# PIC32MK.net
KiCad netlist of a schematic drawn in Altium Designer
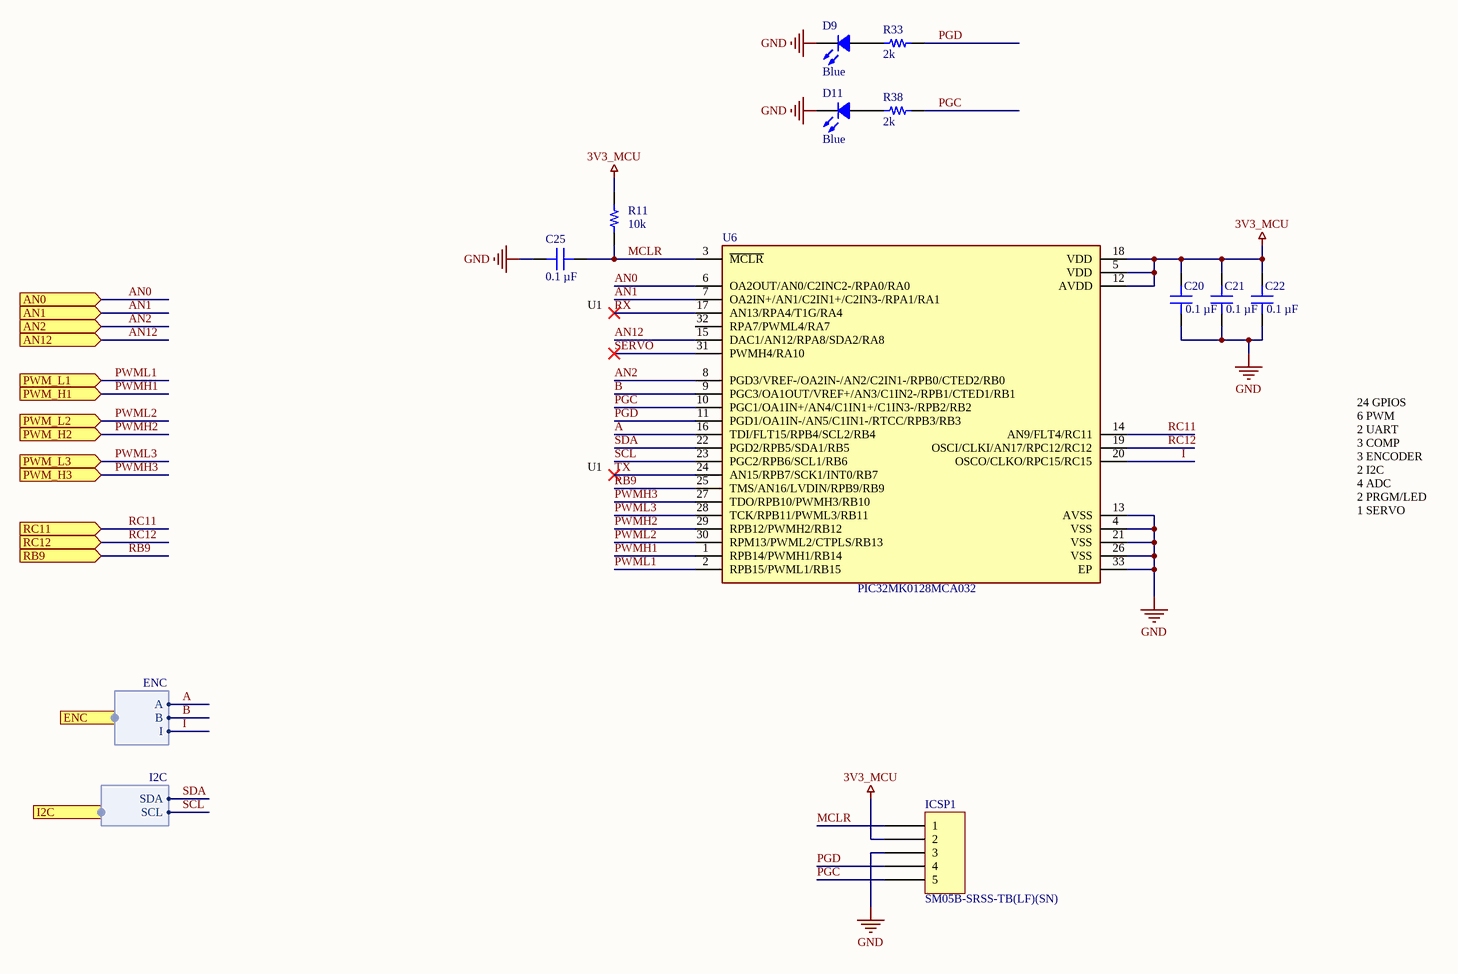
[diagram p0: PIC32MK.SchDoc]

(export (version "E")
  (design (tool "Eeschema 10.0.6"))
  (components
    (comp (ref "C20")
      (value "0.1 µF")
      (footprint "CAP 0402_1005")
      (description "CAP CER 0.1UF 16V X7R 0402")
      (fields (field (name "PART NUMBER") "C0402C104K4RACAUTO") (field (name "MANUFACTURER") "KEMET"))
      (libsource (lib "Celestial Altium Library - altium_library") (part "Capacitor"))
    )
    (comp (ref "C21")
      (value "0.1 µF")
      (footprint "CAP 0402_1005")
      (description "CAP CER 0.1UF 16V X7R 0402")
      (fields (field (name "PART NUMBER") "C0402C104K4RACAUTO") (field (name "MANUFACTURER") "KEMET"))
      (libsource (lib "Celestial Altium Library - altium_library") (part "Capacitor"))
    )
    (comp (ref "C22")
      (value "0.1 µF")
      (footprint "CAP 0402_1005")
      (description "CAP CER 0.1UF 16V X7R 0402")
      (fields (field (name "PART NUMBER") "C0402C104K4RACAUTO") (field (name "MANUFACTURER") "KEMET"))
      (libsource (lib "Celestial Altium Library - altium_library") (part "Capacitor"))
    )
    (comp (ref "C25")
      (value "0.1 µF")
      (footprint "CAP 0402_1005")
      (description "CAP CER 0.1UF 16V X7R 0402")
      (fields (field (name "PART NUMBER") "C0402C104K4RACAUTO") (field (name "MANUFACTURER") "KEMET"))
      (libsource (lib "Celestial Altium Library - altium_library") (part "Capacitor"))
    )
    (comp (ref "D9")
      (value "Blue")
      (footprint "LED 0603_1608 GREEN")
      (description "Blue LED")
      (fields (field (name "PART NUMBER") "XZCDGK53W-8VF") (field (name "MANUFACTURER") "SunLED"))
      (libsource (lib "Celestial Altium Library - altium_library") (part "LED"))
    )
    (comp (ref "D11")
      (value "Blue")
      (footprint "LED 0603_1608 GREEN")
      (description "Blue LED")
      (fields (field (name "PART NUMBER") "XZCDGK53W-8VF") (field (name "MANUFACTURER") "SunLED"))
      (libsource (lib "Celestial Altium Library - altium_library") (part "LED"))
    )
    (comp (ref "ICSP1")
      (value "SM05B-SRSS-TB(LF)(SN)")
      (footprint "JST SM05B-SRSS-TB")
      (description "CONN HEADER SMD R/A 5POS 1MM")
      (fields (field (name "MANUFACTURER") "JST Sales America Inc."))
      (libsource (lib "Celestial Altium Library - altium_library") (part "5 Pin"))
    )
    (comp (ref "R11")
      (value "10k")
      (footprint "RES 0402_1005")
      (description "RES 14.3K OHM 1% 1/10W 0402")
      (fields
        (field (name "PART NUMBER") "RK73H1ETTP1432F")
        (field (name "MANUFACTURER") "KOA Speer Electronics, Inc.")
      )
      (libsource (lib "Celestial Altium Library - altium_library") (part "Resistor"))
    )
    (comp (ref "R33")
      (value "2k")
      (footprint "RES 0402_1005")
      (description "RES 14.3K OHM 1% 1/10W 0402")
      (fields
        (field (name "PART NUMBER") "RK73H1ETTP1432F")
        (field (name "MANUFACTURER") "KOA Speer Electronics, Inc.")
      )
      (libsource (lib "Celestial Altium Library - altium_library") (part "Resistor"))
    )
    (comp (ref "R38")
      (value "2k")
      (footprint "RES 0402_1005")
      (description "RES 14.3K OHM 1% 1/10W 0402")
      (fields
        (field (name "PART NUMBER") "RK73H1ETTP1432F")
        (field (name "MANUFACTURER") "KOA Speer Electronics, Inc.")
      )
      (libsource (lib "Celestial Altium Library - altium_library") (part "Resistor"))
    )
    (comp (ref "U6")
      (value "PIC32MK0128MCA032")
      (footprint "32-QFN_5x5_PIC32")
      (description "PIC32MK Microcontroller IC 32-Bit 120MHz 1MB _1M x 8_ FLASH 32-VQFN_5x5_")
      (fields
        (field (name "MP") "PIC32MK1024MCF064-I/PT")
        (field (name "DIGI-KEY_PART_NUMBER") "PIC32MK1024MCF064-I/PT-ND")
      )
      (libsource (lib "IC") (part "PIC32MK0128MCA032"))
    )
  )
  (nets
    (net (code "3") (name "/A") (class "Default")
      (node (ref "U6") (pin "16") (pinfunction "TDI/FLT15/RPB4/SCL2/RB4_16") (pintype "passive"))
    )
    (net (code "4") (name "/AN0") (class "Default")
      (node (ref "U6") (pin "6") (pinfunction "OA2OUT/AN0/C2INC2-/RPA0/RA0_6") (pintype "passive"))
    )
    (net (code "5") (name "/AN1") (class "Default")
      (node (ref "U6") (pin "7") (pinfunction "OA2IN+/AN1/C2IN1+/C2IN3-/RPA1/RA1_7") (pintype "passive"))
    )
    (net (code "6") (name "/AN2") (class "Default")
      (node (ref "U6") (pin "8") (pinfunction "PGD3/VREF-/OA2IN-/AN2/C2IN1-/RPB0/CTED2/RB0_8") (pintype "passive"))
    )
    (net (code "7") (name "/AN12") (class "Default")
      (node (ref "U6") (pin "15") (pinfunction "DAC1/AN12/RPA8/SDA2/RA8_15") (pintype "passive"))
    )
    (net (code "8") (name "/B") (class "Default")
      (node (ref "U6") (pin "9") (pinfunction "PGC3/OA1OUT/VREF+/AN3/C1IN2-/RPB1/CTED1/RB1_9") (pintype "passive"))
    )
    (net (code "9") (name "/I") (class "Default")
      (node (ref "U6") (pin "20") (pinfunction "OSCO/CLKO/RPC15/RC15_20") (pintype "passive"))
    )
    (net (code "10") (name "/MCLR") (class "Default")
      (node (ref "C25") (pin "1") (pinfunction "1_1") (pintype "passive"))
      (node (ref "ICSP1") (pin "1") (pinfunction "1_1") (pintype "passive"))
      (node (ref "R11") (pin "1") (pinfunction "1_1") (pintype "passive"))
      (node (ref "U6") (pin "3") (pinfunction "~{MCLR}_3") (pintype "passive"))
    )
    (net (code "11") (name "/PGC") (class "Default")
      (node (ref "ICSP1") (pin "5") (pinfunction "5_5") (pintype "passive"))
      (node (ref "R38") (pin "1") (pinfunction "1_1") (pintype "passive"))
      (node (ref "U6") (pin "10") (pinfunction "PGC1/OA1IN+/AN4/C1IN1+/C1IN3-/RPB2/RB2_10") (pintype "passive"))
    )
    (net (code "12") (name "/PGD") (class "Default")
      (node (ref "ICSP1") (pin "4") (pinfunction "4_4") (pintype "passive"))
      (node (ref "R33") (pin "1") (pinfunction "1_1") (pintype "passive"))
      (node (ref "U6") (pin "11") (pinfunction "PGD1/OA1IN-/AN5/C1IN1-/RTCC/RPB3/RB3_11") (pintype "passive"))
    )
    (net (code "13") (name "/PWMH1") (class "Default")
      (node (ref "U6") (pin "1") (pinfunction "RPB14/PWMH1/RB14_1") (pintype "passive"))
    )
    (net (code "14") (name "/PWMH2") (class "Default")
      (node (ref "U6") (pin "29") (pinfunction "RPB12/PWMH2/RB12_29") (pintype "passive"))
    )
    (net (code "15") (name "/PWMH3") (class "Default")
      (node (ref "U6") (pin "27") (pinfunction "TDO/RPB10/PWMH3/RB10_27") (pintype "passive"))
    )
    (net (code "16") (name "/PWML1") (class "Default")
      (node (ref "U6") (pin "2") (pinfunction "RPB15/PWML1/RB15_2") (pintype "passive"))
    )
    (net (code "17") (name "/PWML2") (class "Default")
      (node (ref "U6") (pin "30") (pinfunction "RPM13/PWML2/CTPLS/RB13_30") (pintype "passive"))
    )
    (net (code "18") (name "/PWML3") (class "Default")
      (node (ref "U6") (pin "28") (pinfunction "TCK/RPB11/PWML3/RB11_28") (pintype "passive"))
    )
    (net (code "19") (name "/RB9") (class "Default")
      (node (ref "U6") (pin "25") (pinfunction "TMS/AN16/LVDIN/RPB9/RB9_25") (pintype "passive"))
    )
    (net (code "20") (name "/RC11") (class "Default")
      (node (ref "U6") (pin "14") (pinfunction "AN9/FLT4/RC11_14") (pintype "passive"))
    )
    (net (code "21") (name "/RC12") (class "Default")
      (node (ref "U6") (pin "19") (pinfunction "OSCI/CLKI/AN17/RPC12/RC12_19") (pintype "passive"))
    )
    (net (code "22") (name "/RX") (class "Default")
      (node (ref "U6") (pin "17") (pinfunction "AN13/RPA4/T1G/RA4_17") (pintype "passive+no_connect"))
    )
    (net (code "23") (name "/SCL") (class "Default")
      (node (ref "U6") (pin "23") (pinfunction "PGC2/RPB6/SCL1/RB6_23") (pintype "passive"))
    )
    (net (code "24") (name "/SDA") (class "Default")
      (node (ref "U6") (pin "22") (pinfunction "PGD2/RPB5/SDA1/RB5_22") (pintype "passive"))
    )
    (net (code "25") (name "/SERVO") (class "Default")
      (node (ref "U6") (pin "31") (pinfunction "PWMH4/RA10_31") (pintype "passive+no_connect"))
    )
    (net (code "26") (name "/TX") (class "Default")
      (node (ref "U6") (pin "24") (pinfunction "AN15/RPB7/SCK1/INT0/RB7_24") (pintype "passive+no_connect"))
    )
    (net (code "29") (name "3V3_MCU") (class "Default")
      (node (ref "C20") (pin "2") (pinfunction "2_2") (pintype "passive"))
      (node (ref "C21") (pin "2") (pinfunction "2_2") (pintype "passive"))
      (node (ref "C22") (pin "2") (pinfunction "2_2") (pintype "passive"))
      (node (ref "ICSP1") (pin "2") (pinfunction "2_2") (pintype "passive"))
      (node (ref "R11") (pin "2") (pinfunction "2_2") (pintype "passive"))
      (node (ref "U6") (pin "12") (pinfunction "AVDD_12") (pintype "passive"))
      (node (ref "U6") (pin "18") (pinfunction "VDD_18") (pintype "passive"))
      (node (ref "U6") (pin "5") (pinfunction "VDD_5") (pintype "passive"))
    )
    (net (code "30") (name "GND") (class "Default")
      (node (ref "C20") (pin "1") (pinfunction "1_1") (pintype "passive"))
      (node (ref "C21") (pin "1") (pinfunction "1_1") (pintype "passive"))
      (node (ref "C22") (pin "1") (pinfunction "1_1") (pintype "passive"))
      (node (ref "C25") (pin "2") (pinfunction "2_2") (pintype "passive"))
      (node (ref "D11") (pin "2") (pinfunction "2_2") (pintype "passive"))
      (node (ref "D9") (pin "2") (pinfunction "2_2") (pintype "passive"))
      (node (ref "ICSP1") (pin "3") (pinfunction "3_3") (pintype "passive"))
      (node (ref "U6") (pin "13") (pinfunction "AVSS_13") (pintype "passive"))
      (node (ref "U6") (pin "21") (pinfunction "VSS_21") (pintype "passive"))
      (node (ref "U6") (pin "26") (pinfunction "VSS_26") (pintype "passive"))
      (node (ref "U6") (pin "33") (pinfunction "EP_33") (pintype "passive"))
      (node (ref "U6") (pin "4") (pinfunction "VSS_4") (pintype "passive"))
    )
    (net (code "31") (name "Net-(D9-Pad1)") (class "Default")
      (node (ref "D9") (pin "1") (pinfunction "1_1") (pintype "passive"))
      (node (ref "R33") (pin "2") (pinfunction "2_2") (pintype "passive"))
    )
    (net (code "32") (name "Net-(D11-Pad1)") (class "Default")
      (node (ref "D11") (pin "1") (pinfunction "1_1") (pintype "passive"))
      (node (ref "R38") (pin "2") (pinfunction "2_2") (pintype "passive"))
    )
    (net (code "33") (name "unconnected-(U6-RPA7{slash}PWML4{slash}RA7-Pad32)") (class "Default")
      (node (ref "U6") (pin "32") (pinfunction "RPA7/PWML4/RA7_32") (pintype "passive"))
    )
  )
)
